# DAP-MCU-3.net
KiCad netlist of a schematic drawn in Altium Designer
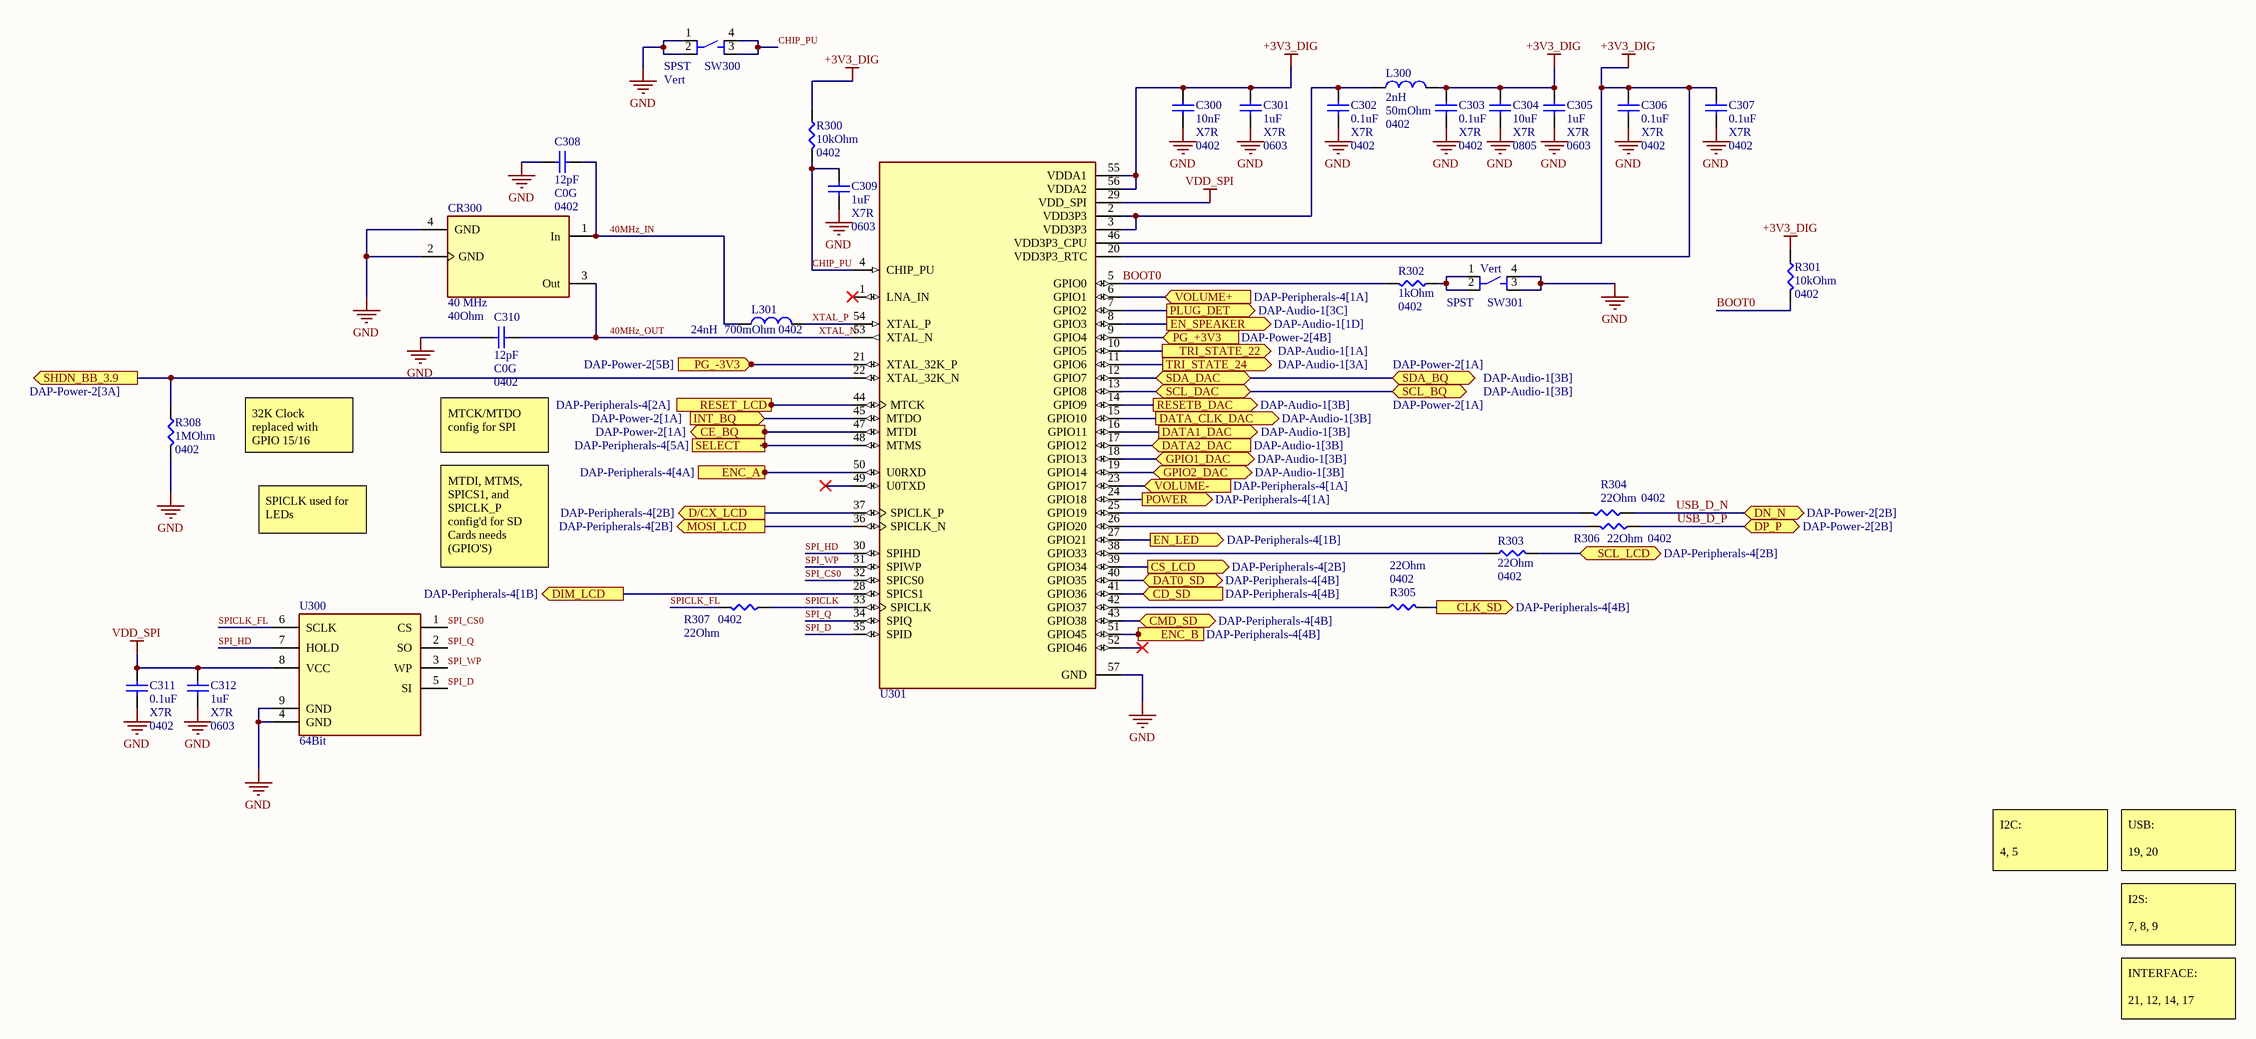
[diagram p0: DAP-MCU-3.SchDoc]

(export (version "E")
  (design (tool "Eeschema 10.0.6"))
  (components
    (comp (ref "C300")
      (value "CAP CER 10000PF 16V X7R 0402")
      (footprint "CAPC1005X55N")
      (fields
        (field (name "<VALUE>") "10nF")
        (field (name "<SPEC>") "X7R")
        (field (name "<FOOTPRINT>") "0402")
        (field (name "CREATOR PROJECT") "aRTy")
      )
      (libsource (lib "aloker-Link") (part "CAP"))
    )
    (comp (ref "C301")
      (value "CAP CER 1UF 25V X7R 0603")
      (footprint "CAPC1608X100N")
      (fields
        (field (name "<VALUE>") "1uF")
        (field (name "<SPEC>") "X7R")
        (field (name "<FOOTPRINT>") "0603")
        (field (name "CREATOR PROJECT") "DAP")
      )
      (libsource (lib "aloker-Link") (part "CAP"))
    )
    (comp (ref "C302")
      (value "CAP CER 0.1UF 50V X7R 0402")
      (footprint "CAPC1005X60N")
      (fields
        (field (name "<VALUE>") "0.1uF")
        (field (name "<SPEC>") "X7R")
        (field (name "<FOOTPRINT>") "0402")
        (field (name "CREATOR PROJECT") "DAP")
      )
      (libsource (lib "aloker-Link") (part "CAP"))
    )
    (comp (ref "C303")
      (value "CAP CER 0.1UF 50V X7R 0402")
      (footprint "CAPC1005X60N")
      (fields
        (field (name "<VALUE>") "0.1uF")
        (field (name "<SPEC>") "X7R")
        (field (name "<FOOTPRINT>") "0402")
        (field (name "CREATOR PROJECT") "DAP")
      )
      (libsource (lib "aloker-Link") (part "CAP"))
    )
    (comp (ref "C304")
      (value "CAP CER 10UF 10V X7R 0805")
      (footprint "CAPC2012X140N")
      (fields
        (field (name "<VALUE>") "10uF")
        (field (name "<SPEC>") "X7R")
        (field (name "<FOOTPRINT>") "0805")
        (field (name "CREATOR PROJECT") "DAP")
      )
      (libsource (lib "aloker-Link") (part "CAP"))
    )
    (comp (ref "C305")
      (value "CAP CER 1UF 25V X7R 0603")
      (footprint "CAPC1608X100N")
      (fields
        (field (name "<VALUE>") "1uF")
        (field (name "<SPEC>") "X7R")
        (field (name "<FOOTPRINT>") "0603")
        (field (name "CREATOR PROJECT") "DAP")
      )
      (libsource (lib "aloker-Link") (part "CAP"))
    )
    (comp (ref "C306")
      (value "CAP CER 0.1UF 50V X7R 0402")
      (footprint "CAPC1005X60N")
      (fields
        (field (name "<VALUE>") "0.1uF")
        (field (name "<SPEC>") "X7R")
        (field (name "<FOOTPRINT>") "0402")
        (field (name "CREATOR PROJECT") "DAP")
      )
      (libsource (lib "aloker-Link") (part "CAP"))
    )
    (comp (ref "C307")
      (value "CAP CER 0.1UF 50V X7R 0402")
      (footprint "CAPC1005X60N")
      (fields
        (field (name "<VALUE>") "0.1uF")
        (field (name "<SPEC>") "X7R")
        (field (name "<FOOTPRINT>") "0402")
        (field (name "CREATOR PROJECT") "DAP")
      )
      (libsource (lib "aloker-Link") (part "CAP"))
    )
    (comp (ref "C308")
      (value "CAP CER 12PF 50V C0G/NP0 0402")
      (footprint "CAPC1005X60N")
      (fields
        (field (name "<VALUE>") "12pF")
        (field (name "<SPEC>") "C0G")
        (field (name "<FOOTPRINT>") "0402")
        (field (name "CREATOR PROJECT") "DAP")
      )
      (libsource (lib "aloker-Link") (part "CAP"))
    )
    (comp (ref "C309")
      (value "CAP CER 1UF 25V X7R 0603")
      (footprint "CAPC1608X100N")
      (fields
        (field (name "<VALUE>") "1uF")
        (field (name "<SPEC>") "X7R")
        (field (name "<FOOTPRINT>") "0603")
        (field (name "CREATOR PROJECT") "DAP")
      )
      (libsource (lib "aloker-Link") (part "CAP"))
    )
    (comp (ref "C310")
      (value "CAP CER 12PF 50V C0G/NP0 0402")
      (footprint "CAPC1005X60N")
      (fields
        (field (name "<VALUE>") "12pF")
        (field (name "<SPEC>") "C0G")
        (field (name "<FOOTPRINT>") "0402")
        (field (name "CREATOR PROJECT") "DAP")
      )
      (libsource (lib "aloker-Link") (part "CAP"))
    )
    (comp (ref "C311")
      (value "CAP CER 0.1UF 50V X7R 0402")
      (footprint "CAPC1005X60N")
      (fields
        (field (name "<VALUE>") "0.1uF")
        (field (name "<SPEC>") "X7R")
        (field (name "<FOOTPRINT>") "0402")
        (field (name "CREATOR PROJECT") "DAP")
      )
      (libsource (lib "aloker-Link") (part "CAP"))
    )
    (comp (ref "C312")
      (value "CAP CER 1UF 25V X7R 0603")
      (footprint "CAPC1608X100N")
      (fields
        (field (name "<VALUE>") "1uF")
        (field (name "<SPEC>") "X7R")
        (field (name "<FOOTPRINT>") "0603")
        (field (name "CREATOR PROJECT") "DAP")
      )
      (libsource (lib "aloker-Link") (part "CAP"))
    )
    (comp (ref "CR300")
      (value "CRYSTAL 40.0000MHZ 10PF SMD")
      (footprint "CRYST_ECS-400")
      (fields
        (field (name "<VALUE>") "40 MHz")
        (field (name "<SPEC>") "40Ohm")
        (field (name "CREATOR PROJECT") "DAP")
      )
      (libsource (lib "aloker-Link") (part "CRYSTAL"))
    )
    (comp (ref "L300")
      (value "FIXED IND 2NH 1A 50 MOHM SMD")
      (footprint "IND_MHQ100507")
      (fields
        (field (name "<VALUE>") "2nH")
        (field (name "<SPEC>") "50mOhm")
        (field (name "<FOOTPRINT>") "0402")
        (field (name "CREATOR PROJECT") "DAP")
      )
      (libsource (lib "aloker-Link") (part "IND"))
    )
    (comp (ref "L301")
      (value "FIXED IND 24NH 250MA 700 MOHM")
      (footprint "IND_MHQ100507")
      (fields
        (field (name "<VALUE>") "24nH")
        (field (name "<SPEC>") "700mOhm")
        (field (name "<FOOTPRINT>") "0402")
        (field (name "CREATOR PROJECT") "DAP")
      )
      (libsource (lib "aloker-Link") (part "IND"))
    )
    (comp (ref "R300")
      (value "RES SMD 10K OHM 1% 1/16W 0402")
      (footprint "RESC1005X40N")
      (fields
        (field (name "<VALUE>") "10kOhm")
        (field (name "<FOOTPRINT>") "0402")
        (field (name "CREATOR PROJECT") "DAP")
      )
      (libsource (lib "aloker-Link") (part "RES"))
    )
    (comp (ref "R301")
      (value "RES SMD 10K OHM 1% 1/16W 0402")
      (footprint "RESC1005X40N")
      (fields
        (field (name "<VALUE>") "10kOhm")
        (field (name "<FOOTPRINT>") "0402")
        (field (name "CREATOR PROJECT") "DAP")
      )
      (libsource (lib "aloker-Link") (part "RES"))
    )
    (comp (ref "R302")
      (value "RES SMD 1K OHM 0.1% 1/16W 0402")
      (footprint "RESC1005X40N")
      (fields
        (field (name "<VALUE>") "1kOhm")
        (field (name "<FOOTPRINT>") "0402")
        (field (name "CREATOR PROJECT") "aRTy")
      )
      (libsource (lib "aloker-Link") (part "RES"))
    )
    (comp (ref "R303")
      (value "RES 22 OHM 1% 1/16W 0402")
      (footprint "RESC1005X40N")
      (fields
        (field (name "<VALUE>") "22Ohm")
        (field (name "<FOOTPRINT>") "0402")
        (field (name "CREATOR PROJECT") "DAP")
      )
      (libsource (lib "aloker-Link") (part "RES"))
    )
    (comp (ref "R304")
      (value "RES 22 OHM 1% 1/16W 0402")
      (footprint "RESC1005X40N")
      (fields
        (field (name "<VALUE>") "22Ohm")
        (field (name "<FOOTPRINT>") "0402")
        (field (name "CREATOR PROJECT") "DAP")
      )
      (libsource (lib "aloker-Link") (part "RES"))
    )
    (comp (ref "R305")
      (value "RES 22 OHM 1% 1/16W 0402")
      (footprint "RESC1005X40N")
      (fields
        (field (name "<VALUE>") "22Ohm")
        (field (name "<FOOTPRINT>") "0402")
        (field (name "CREATOR PROJECT") "DAP")
      )
      (libsource (lib "aloker-Link") (part "RES"))
    )
    (comp (ref "R306")
      (value "RES 22 OHM 1% 1/16W 0402")
      (footprint "RESC1005X40N")
      (fields
        (field (name "<VALUE>") "22Ohm")
        (field (name "<FOOTPRINT>") "0402")
        (field (name "CREATOR PROJECT") "DAP")
      )
      (libsource (lib "aloker-Link") (part "RES"))
    )
    (comp (ref "R307")
      (value "RES 22 OHM 1% 1/16W 0402")
      (footprint "RESC1005X40N")
      (fields
        (field (name "<VALUE>") "22Ohm")
        (field (name "<FOOTPRINT>") "0402")
        (field (name "CREATOR PROJECT") "DAP")
      )
      (libsource (lib "aloker-Link") (part "RES"))
    )
    (comp (ref "R308")
      (value "RES SMD 1M OHM 0.1% 1/16W 0402")
      (footprint "RESC1005X40N")
      (fields
        (field (name "<VALUE>") "1MOhm")
        (field (name "<FOOTPRINT>") "0402")
        (field (name "CREATOR PROJECT") "DAP")
      )
      (libsource (lib "aloker-Link") (part "RES"))
    )
    (comp (ref "SW300")
      (value "SWITCH TACTILE SPST-NO 0.05A 16V")
      (footprint "SW_PTS810_SJM_250_SMTR_LFS")
      (fields
        (field (name "MF") "C&K")
        (field (name "MP") "PTS810 SJM 250 SMTR LFS")
        (field (name "<VALUE>") "SPST")
        (field (name "<FOOTPRINT>") "Vert")
        (field (name "CREATOR PROJECT") "DAP")
      )
      (libsource (lib "aloker-Link") (part "PTS810_SJM_250_SMTR_LFS"))
    )
    (comp (ref "SW301")
      (value "SWITCH TACTILE SPST-NO 0.05A 16V")
      (footprint "SW_PTS810_SJM_250_SMTR_LFS")
      (fields
        (field (name "MF") "C&K")
        (field (name "MP") "PTS810 SJM 250 SMTR LFS")
        (field (name "<VALUE>") "SPST")
        (field (name "<FOOTPRINT>") "Vert")
        (field (name "CREATOR PROJECT") "DAP")
      )
      (libsource (lib "aloker-Link") (part "PTS810_SJM_250_SMTR_LFS"))
    )
    (comp (ref "U300")
      (value "IC FLASH 64MBIT SPI/QUAD 8WSON")
      (footprint "SON127P600X500X80-9N")
      (fields (field (name "<VALUE>") "64Bit") (field (name "CREATOR PROJECT") "DAP"))
      (libsource (lib "aloker-Link") (part "FLASH_WSON8"))
    )
    (comp (ref "U301")
      (value "ESP32-S3")
      (footprint "IC_ESP32-S3")
      (fields (field (name "MF") "Espressif Systems") (field (name "CREATOR PROJECT") "DAP"))
      (libsource (lib "aloker-Link") (part "ESP32-S3"))
    )
  )
  (nets
    (net (code "1") (name "+3V3_DIG") (class "Default")
      (node (ref "C300") (pin "2") (pinfunction "2_2") (pintype "passive"))
      (node (ref "C301") (pin "2") (pinfunction "2_2") (pintype "passive"))
      (node (ref "C303") (pin "2") (pinfunction "2_2") (pintype "passive"))
      (node (ref "C304") (pin "2") (pinfunction "2_2") (pintype "passive"))
      (node (ref "C305") (pin "2") (pinfunction "2_2") (pintype "passive"))
      (node (ref "C306") (pin "2") (pinfunction "2_2") (pintype "passive"))
      (node (ref "C307") (pin "2") (pinfunction "2_2") (pintype "passive"))
      (node (ref "L300") (pin "2") (pinfunction "2_2") (pintype "passive"))
      (node (ref "R300") (pin "2") (pinfunction "2_2") (pintype "passive"))
      (node (ref "R301") (pin "2") (pinfunction "2_2") (pintype "passive"))
      (node (ref "U301") (pin "20") (pinfunction "VDD3P3_RTC_20") (pintype "power_in"))
      (node (ref "U301") (pin "46") (pinfunction "VDD3P3_CPU_46") (pintype "power_in"))
      (node (ref "U301") (pin "55") (pinfunction "VDDA1_55") (pintype "power_in"))
      (node (ref "U301") (pin "56") (pinfunction "VDDA2_56") (pintype "power_in"))
    )
    (net (code "2") (name "/40MHz_IN") (class "Default")
      (node (ref "C308") (pin "1") (pinfunction "1_1") (pintype "passive"))
      (node (ref "CR300") (pin "1") (pinfunction "In_1") (pintype "passive"))
      (node (ref "L301") (pin "1") (pinfunction "1_1") (pintype "passive"))
    )
    (net (code "3") (name "/40MHz_OUT") (class "Default")
      (node (ref "C310") (pin "1") (pinfunction "1_1") (pintype "passive"))
      (node (ref "CR300") (pin "3") (pinfunction "Out_3") (pintype "passive"))
      (node (ref "U301") (pin "53") (pinfunction "XTAL_N_53") (pintype "output"))
    )
    (net (code "4") (name "/BOOT0") (class "Default")
      (node (ref "R301") (pin "1") (pinfunction "1_1") (pintype "passive"))
      (node (ref "R302") (pin "1") (pinfunction "1_1") (pintype "passive"))
      (node (ref "U301") (pin "5") (pinfunction "GPIO0_5") (pintype "bidirectional"))
    )
    (net (code "5") (name "/CD_SD") (class "Default")
      (node (ref "U301") (pin "41") (pinfunction "GPIO36_41") (pintype "bidirectional"))
    )
    (net (code "6") (name "/CE_BQ") (class "Default")
      (node (ref "U301") (pin "47") (pinfunction "MTDI_47") (pintype "bidirectional"))
    )
    (net (code "7") (name "/CHIP_PU") (class "Default")
      (node (ref "C309") (pin "2") (pinfunction "2_2") (pintype "passive"))
      (node (ref "R300") (pin "1") (pinfunction "1_1") (pintype "passive"))
      (node (ref "SW300") (pin "3") (pinfunction "3_3") (pintype "passive"))
      (node (ref "SW300") (pin "4") (pinfunction "4_4") (pintype "passive"))
      (node (ref "U301") (pin "4") (pinfunction "CHIP_PU_4") (pintype "input"))
    )
    (net (code "8") (name "/CLK_SD") (class "Default")
      (node (ref "R305") (pin "1") (pinfunction "1_1") (pintype "passive"))
    )
    (net (code "9") (name "/CMD_SD") (class "Default")
      (node (ref "U301") (pin "43") (pinfunction "GPIO38_43") (pintype "bidirectional"))
    )
    (net (code "10") (name "/CS_LCD") (class "Default")
      (node (ref "U301") (pin "39") (pinfunction "GPIO34_39") (pintype "bidirectional"))
    )
    (net (code "11") (name "/DAT0_SD") (class "Default")
      (node (ref "U301") (pin "40") (pinfunction "GPIO35_40") (pintype "bidirectional"))
    )
    (net (code "12") (name "/DATA1_DAC") (class "Default")
      (node (ref "U301") (pin "16") (pinfunction "GPIO11_16") (pintype "bidirectional"))
    )
    (net (code "13") (name "/DATA2_DAC") (class "Default")
      (node (ref "U301") (pin "17") (pinfunction "GPIO12_17") (pintype "bidirectional"))
    )
    (net (code "14") (name "/DATA_CLK_DAC") (class "Default")
      (node (ref "U301") (pin "15") (pinfunction "GPIO10_15") (pintype "bidirectional"))
    )
    (net (code "15") (name "/DIM_LCD") (class "Default")
      (node (ref "U301") (pin "28") (pinfunction "SPICS1_28") (pintype "bidirectional"))
    )
    (net (code "16") (name "/D{slash}CX_LCD") (class "Default")
      (node (ref "U301") (pin "37") (pinfunction "SPICLK_P_37") (pintype "bidirectional"))
    )
    (net (code "17") (name "/ENC_A") (class "Default")
      (node (ref "U301") (pin "50") (pinfunction "U0RXD_50") (pintype "bidirectional"))
    )
    (net (code "18") (name "/ENC_B") (class "Default")
      (node (ref "U301") (pin "51") (pinfunction "GPIO45_51") (pintype "bidirectional"))
    )
    (net (code "19") (name "/EN_LED") (class "Default")
      (node (ref "U301") (pin "27") (pinfunction "GPIO21_27") (pintype "bidirectional"))
    )
    (net (code "20") (name "/EN_SPEAKER") (class "Default")
      (node (ref "U301") (pin "8") (pinfunction "GPIO3_8") (pintype "bidirectional"))
    )
    (net (code "21") (name "/GPIO1_DAC") (class "Default")
      (node (ref "U301") (pin "18") (pinfunction "GPIO13_18") (pintype "bidirectional"))
    )
    (net (code "22") (name "/GPIO2_DAC") (class "Default")
      (node (ref "U301") (pin "19") (pinfunction "GPIO14_19") (pintype "bidirectional"))
    )
    (net (code "23") (name "/INT_BQ") (class "Default")
      (node (ref "U301") (pin "45") (pinfunction "MTDO_45") (pintype "bidirectional"))
    )
    (net (code "24") (name "/MOSI_LCD") (class "Default")
      (node (ref "U301") (pin "36") (pinfunction "SPICLK_N_36") (pintype "bidirectional"))
    )
    (net (code "25") (name "/PG_+3V3") (class "Default")
      (node (ref "U301") (pin "9") (pinfunction "GPIO4_9") (pintype "bidirectional"))
    )
    (net (code "26") (name "/PG_-3V3") (class "Default")
      (node (ref "U301") (pin "21") (pinfunction "XTAL_32K_P_21") (pintype "bidirectional"))
    )
    (net (code "27") (name "/PLUG_DET") (class "Default")
      (node (ref "U301") (pin "7") (pinfunction "GPIO2_7") (pintype "bidirectional"))
    )
    (net (code "28") (name "/POWER") (class "Default")
      (node (ref "U301") (pin "24") (pinfunction "GPIO18_24") (pintype "bidirectional"))
    )
    (net (code "29") (name "/RESETB_DAC") (class "Default")
      (node (ref "U301") (pin "14") (pinfunction "GPIO9_14") (pintype "bidirectional"))
    )
    (net (code "30") (name "/RESET_LCD") (class "Default")
      (node (ref "U301") (pin "44") (pinfunction "MTCK_44") (pintype "bidirectional"))
    )
    (net (code "31") (name "/SCL_BQ") (class "Default")
      (node (ref "U301") (pin "13") (pinfunction "GPIO8_13") (pintype "bidirectional"))
    )
    (net (code "32") (name "/SCL_LCD") (class "Default")
      (node (ref "R303") (pin "1") (pinfunction "1_1") (pintype "passive"))
    )
    (net (code "33") (name "/SDA_BQ") (class "Default")
      (node (ref "U301") (pin "12") (pinfunction "GPIO7_12") (pintype "bidirectional"))
    )
    (net (code "34") (name "/SELECT") (class "Default")
      (node (ref "U301") (pin "48") (pinfunction "MTMS_48") (pintype "bidirectional"))
    )
    (net (code "35") (name "/SHDN_BB_3.9") (class "Default")
      (node (ref "R308") (pin "2") (pinfunction "2_2") (pintype "passive"))
      (node (ref "U301") (pin "22") (pinfunction "XTAL_32K_N_22") (pintype "bidirectional"))
    )
    (net (code "36") (name "/SPICLK") (class "Default")
      (node (ref "R307") (pin "2") (pinfunction "2_2") (pintype "passive"))
      (node (ref "U301") (pin "33") (pinfunction "SPICLK_33") (pintype "bidirectional"))
    )
    (net (code "37") (name "/SPICLK_FL") (class "Default")
      (node (ref "R307") (pin "1") (pinfunction "1_1") (pintype "passive"))
      (node (ref "U300") (pin "6") (pinfunction "SCLK_6") (pintype "passive"))
    )
    (net (code "38") (name "/SPI_CS0") (class "Default")
      (node (ref "U300") (pin "1") (pinfunction "CS_1") (pintype "passive"))
      (node (ref "U301") (pin "32") (pinfunction "SPICS0_32") (pintype "bidirectional"))
    )
    (net (code "39") (name "/SPI_D") (class "Default")
      (node (ref "U300") (pin "5") (pinfunction "SI_5") (pintype "passive"))
      (node (ref "U301") (pin "35") (pinfunction "SPID_35") (pintype "bidirectional"))
    )
    (net (code "40") (name "/SPI_HD") (class "Default")
      (node (ref "U300") (pin "7") (pinfunction "HOLD_7") (pintype "passive"))
      (node (ref "U301") (pin "30") (pinfunction "SPIHD_30") (pintype "bidirectional"))
    )
    (net (code "41") (name "/SPI_Q") (class "Default")
      (node (ref "U300") (pin "2") (pinfunction "SO_2") (pintype "passive"))
      (node (ref "U301") (pin "34") (pinfunction "SPIQ_34") (pintype "bidirectional"))
    )
    (net (code "42") (name "/SPI_WP") (class "Default")
      (node (ref "U300") (pin "3") (pinfunction "WP_3") (pintype "passive"))
      (node (ref "U301") (pin "31") (pinfunction "SPIWP_31") (pintype "bidirectional"))
    )
    (net (code "43") (name "/TRI_STATE_22") (class "Default")
      (node (ref "U301") (pin "10") (pinfunction "GPIO5_10") (pintype "bidirectional"))
    )
    (net (code "44") (name "/TRI_STATE_24") (class "Default")
      (node (ref "U301") (pin "11") (pinfunction "GPIO6_11") (pintype "bidirectional"))
    )
    (net (code "45") (name "/USB_D_N") (class "Default")
      (node (ref "R304") (pin "2") (pinfunction "2_2") (pintype "passive"))
    )
    (net (code "46") (name "/USB_D_P") (class "Default")
      (node (ref "R306") (pin "2") (pinfunction "2_2") (pintype "passive"))
    )
    (net (code "47") (name "/VOLUME+") (class "Default")
      (node (ref "U301") (pin "6") (pinfunction "GPIO1_6") (pintype "bidirectional"))
    )
    (net (code "48") (name "/VOLUME-") (class "Default")
      (node (ref "U301") (pin "23") (pinfunction "GPIO17_23") (pintype "bidirectional"))
    )
    (net (code "49") (name "/XTAL_P") (class "Default")
      (node (ref "L301") (pin "2") (pinfunction "2_2") (pintype "passive"))
      (node (ref "U301") (pin "54") (pinfunction "XTAL_P_54") (pintype "input"))
    )
    (net (code "50") (name "GND") (class "Default")
      (node (ref "C300") (pin "1") (pinfunction "1_1") (pintype "passive"))
      (node (ref "C301") (pin "1") (pinfunction "1_1") (pintype "passive"))
      (node (ref "C302") (pin "1") (pinfunction "1_1") (pintype "passive"))
      (node (ref "C303") (pin "1") (pinfunction "1_1") (pintype "passive"))
      (node (ref "C304") (pin "1") (pinfunction "1_1") (pintype "passive"))
      (node (ref "C305") (pin "1") (pinfunction "1_1") (pintype "passive"))
      (node (ref "C306") (pin "1") (pinfunction "1_1") (pintype "passive"))
      (node (ref "C307") (pin "1") (pinfunction "1_1") (pintype "passive"))
      (node (ref "C308") (pin "2") (pinfunction "2_2") (pintype "passive"))
      (node (ref "C309") (pin "1") (pinfunction "1_1") (pintype "passive"))
      (node (ref "C310") (pin "2") (pinfunction "2_2") (pintype "passive"))
      (node (ref "C311") (pin "1") (pinfunction "1_1") (pintype "passive"))
      (node (ref "C312") (pin "1") (pinfunction "1_1") (pintype "passive"))
      (node (ref "CR300") (pin "2") (pinfunction "GND_2") (pintype "power_in"))
      (node (ref "CR300") (pin "4") (pinfunction "GND_4") (pintype "power_in"))
      (node (ref "R308") (pin "1") (pinfunction "1_1") (pintype "passive"))
      (node (ref "SW300") (pin "1") (pinfunction "1_1") (pintype "passive"))
      (node (ref "SW300") (pin "2") (pinfunction "2_2") (pintype "passive"))
      (node (ref "SW301") (pin "3") (pinfunction "3_3") (pintype "passive"))
      (node (ref "SW301") (pin "4") (pinfunction "4_4") (pintype "passive"))
      (node (ref "U300") (pin "4") (pinfunction "GND_4") (pintype "power_in"))
      (node (ref "U300") (pin "9") (pinfunction "GND_9") (pintype "passive"))
      (node (ref "U301") (pin "57") (pinfunction "GND_57") (pintype "power_in"))
    )
    (net (code "51") (name "Net-(C302-Pad2)") (class "Default")
      (node (ref "C302") (pin "2") (pinfunction "2_2") (pintype "passive"))
      (node (ref "L300") (pin "1") (pinfunction "1_1") (pintype "passive"))
      (node (ref "U301") (pin "2") (pinfunction "VDD3P3_2") (pintype "power_in"))
      (node (ref "U301") (pin "3") (pinfunction "VDD3P3_3") (pintype "power_in"))
    )
    (net (code "52") (name "Net-(R302-Pad2)") (class "Default")
      (node (ref "R302") (pin "2") (pinfunction "2_2") (pintype "passive"))
      (node (ref "SW301") (pin "1") (pinfunction "1_1") (pintype "passive"))
      (node (ref "SW301") (pin "2") (pinfunction "2_2") (pintype "passive"))
    )
    (net (code "53") (name "Net-(U301-GPIO19)") (class "Default")
      (node (ref "R304") (pin "1") (pinfunction "1_1") (pintype "passive"))
      (node (ref "U301") (pin "25") (pinfunction "GPIO19_25") (pintype "bidirectional"))
    )
    (net (code "54") (name "Net-(U301-GPIO20)") (class "Default")
      (node (ref "R306") (pin "1") (pinfunction "1_1") (pintype "passive"))
      (node (ref "U301") (pin "26") (pinfunction "GPIO20_26") (pintype "bidirectional"))
    )
    (net (code "55") (name "Net-(U301-GPIO33)") (class "Default")
      (node (ref "R303") (pin "2") (pinfunction "2_2") (pintype "passive"))
      (node (ref "U301") (pin "38") (pinfunction "GPIO33_38") (pintype "bidirectional"))
    )
    (net (code "56") (name "Net-(U301-GPIO37)") (class "Default")
      (node (ref "R305") (pin "2") (pinfunction "2_2") (pintype "passive"))
      (node (ref "U301") (pin "42") (pinfunction "GPIO37_42") (pintype "bidirectional"))
    )
    (net (code "57") (name "VDD_SPI") (class "Default")
      (node (ref "C311") (pin "2") (pinfunction "2_2") (pintype "passive"))
      (node (ref "C312") (pin "2") (pinfunction "2_2") (pintype "passive"))
      (node (ref "U300") (pin "8") (pinfunction "VCC_8") (pintype "passive"))
      (node (ref "U301") (pin "29") (pinfunction "VDD_SPI_29") (pintype "power_in"))
    )
    (net (code "58") (name "unconnected-(U301-GPIO46-Pad52)") (class "Default")
      (node (ref "U301") (pin "52") (pinfunction "GPIO46_52") (pintype "bidirectional"))
    )
    (net (code "59") (name "unconnected-(U301-LNA_IN-Pad1)") (class "Default")
      (node (ref "U301") (pin "1") (pinfunction "LNA_IN_1") (pintype "bidirectional+no_connect"))
    )
    (net (code "60") (name "unconnected-(U301-U0TXD-Pad49)") (class "Default")
      (node (ref "U301") (pin "49") (pinfunction "U0TXD_49") (pintype "bidirectional+no_connect"))
    )
  )
)
